# VentaConnected_ESP8266_V0_01_2018-09-03.net
KiCad netlist of a schematic drawn in EAGLE
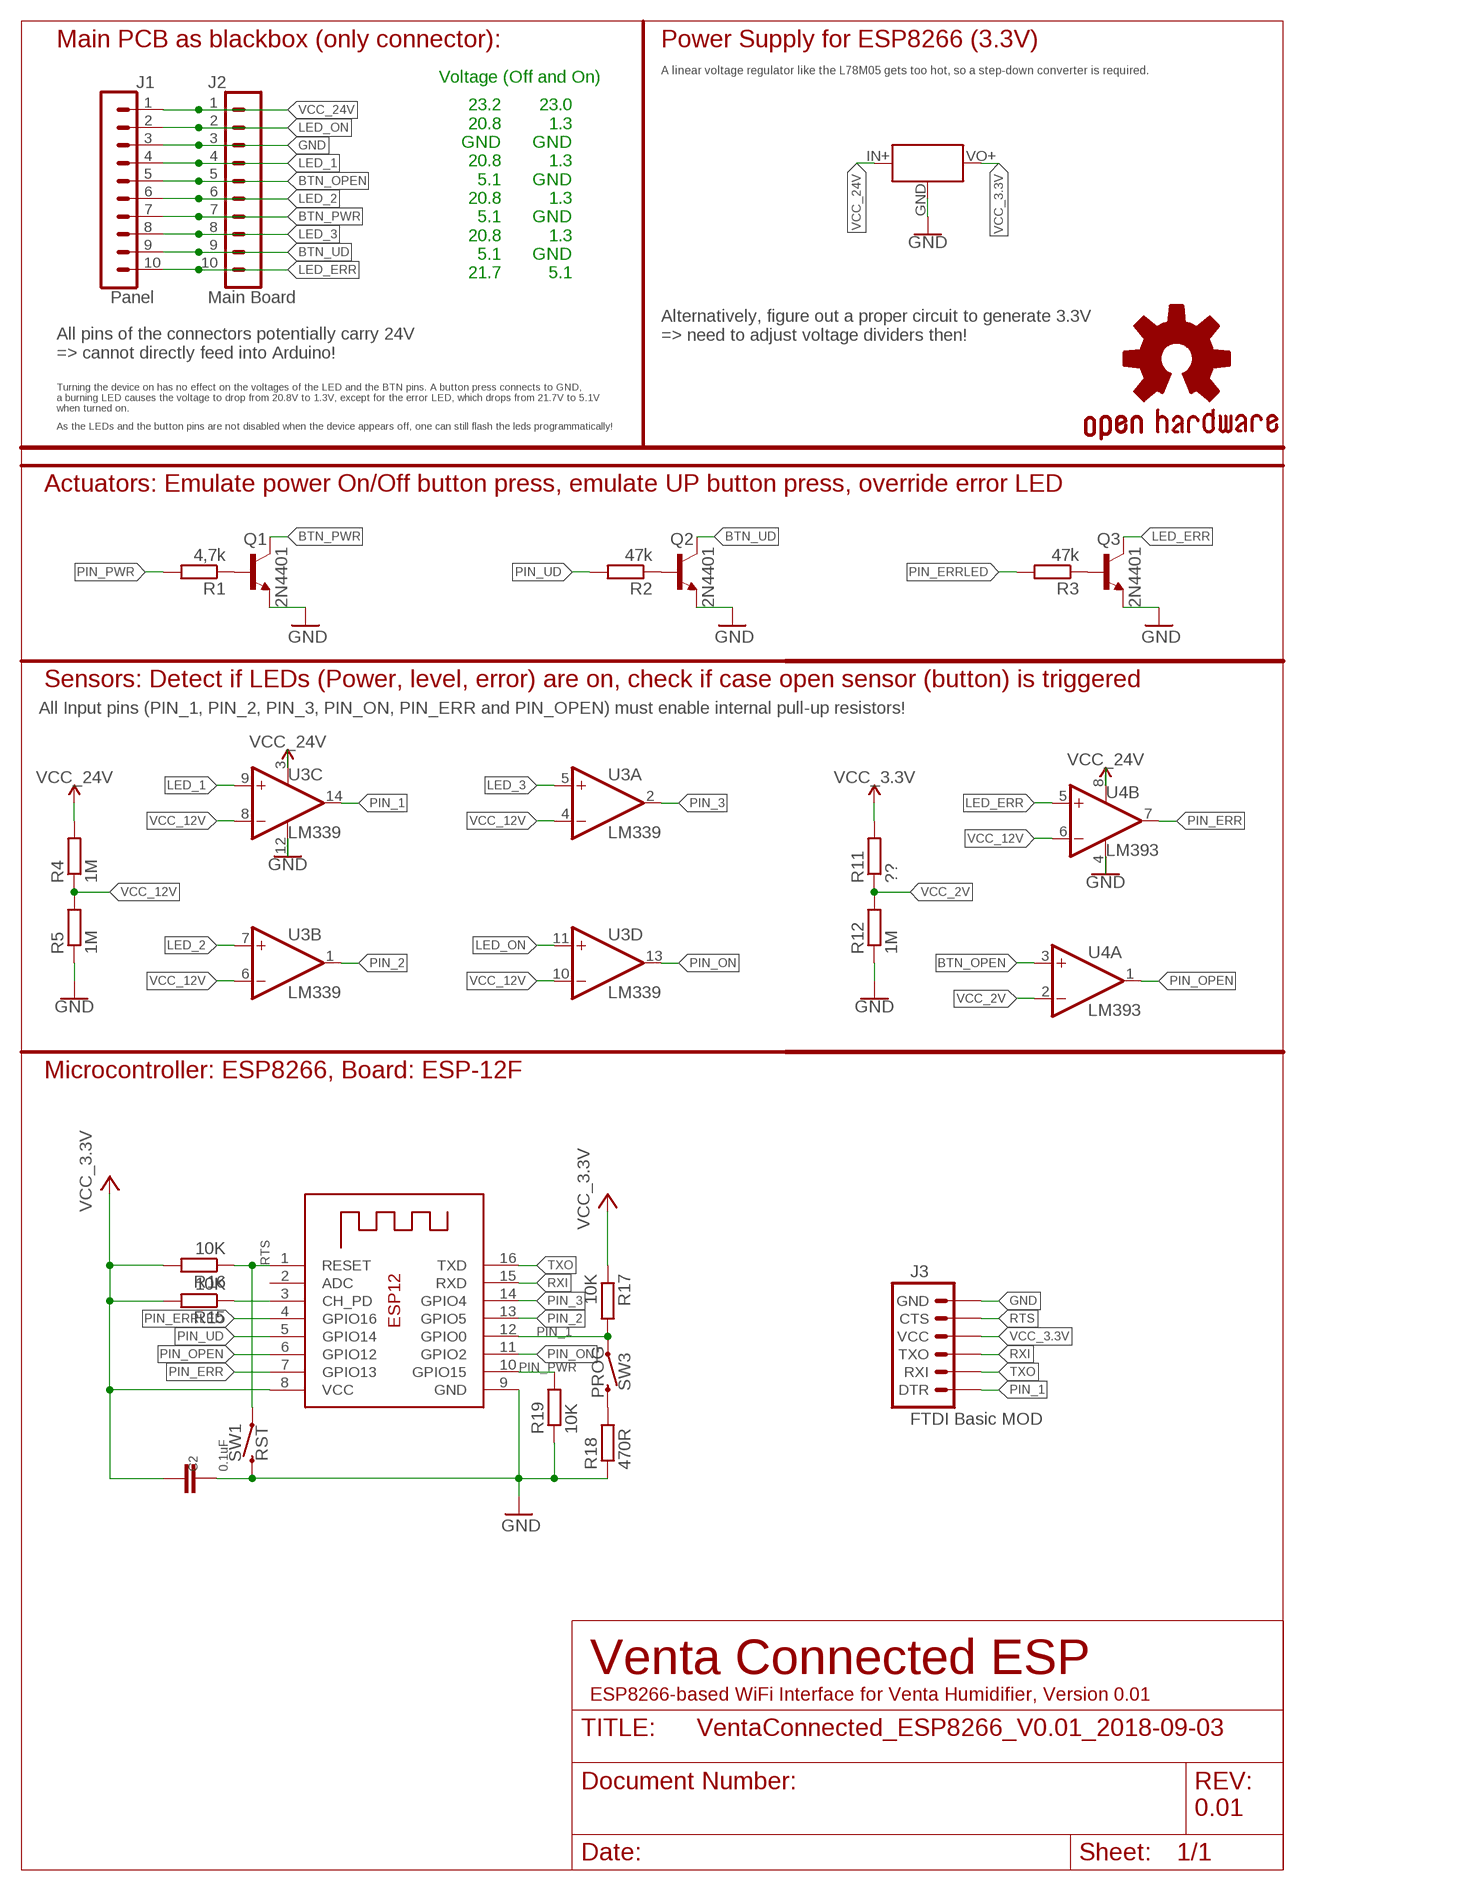
[diagram p0: schematic, sheet 1]

(export (version "E")
  (design (tool "Eeschema 10.0.6"))
  (components
    (comp (ref "C2")
      (value "0.1uF")
      (footprint "eagle-import:C0805")
      (libsource (lib "eagle-import") (part "C-EUC0805"))
    )
    (comp (ref "GOLD_ORB_SM1")
      (value "OSHWLOGO_GOLD_ORB_SM")
      (footprint "eagle-import:OSHW2")
      (libsource (lib "eagle-import") (part "OSHWLOGO_GOLD_ORB_SM"))
    )
    (comp (ref "J1")
      (value "Panel")
      (footprint "eagle-import:2X5-SHROUDED")
      (libsource (lib "eagle-import") (part "CONN_05X2SHD"))
    )
    (comp (ref "J2")
      (value "Main Board")
      (footprint "eagle-import:2X5")
      (libsource (lib "eagle-import") (part "CONN_05X2PTH"))
    )
    (comp (ref "J3")
      (value "FTDI Basic MOD")
      (footprint "eagle-import:1X06")
      (libsource (lib "eagle-import") (part "ARDUINO_SERIAL_PROGRAMPTH"))
    )
    (comp (ref "Q1")
      (value "2N4401")
      (footprint "eagle-import:SOT23-BEC")
      (libsource (lib "eagle-import") (part "-NPN-SOT23-BECMMBT4401LT1"))
    )
    (comp (ref "Q2")
      (value "2N4401")
      (footprint "eagle-import:SOT23-BEC")
      (libsource (lib "eagle-import") (part "-NPN-SOT23-BECMMBT4401LT1"))
    )
    (comp (ref "Q3")
      (value "2N4401")
      (footprint "eagle-import:SOT23-BEC")
      (libsource (lib "eagle-import") (part "-NPN-SOT23-BECMMBT4401LT1"))
    )
    (comp (ref "R1")
      (value "4,7k")
      (footprint "eagle-import:R0805")
      (libsource (lib "eagle-import") (part "resistor_348_R-EU_R0805"))
    )
    (comp (ref "R2")
      (value "47k")
      (footprint "eagle-import:R0805")
      (libsource (lib "eagle-import") (part "resistor_348_R-EU_R0805"))
    )
    (comp (ref "R3")
      (value "47k")
      (footprint "eagle-import:R0805")
      (libsource (lib "eagle-import") (part "resistor_348_R-EU_R0805"))
    )
    (comp (ref "R4")
      (value "1M")
      (footprint "eagle-import:R0805")
      (libsource (lib "eagle-import") (part "resistor_348_R-EU_R0805"))
    )
    (comp (ref "R5")
      (value "1M")
      (footprint "eagle-import:R0805")
      (libsource (lib "eagle-import") (part "resistor_348_R-EU_R0805"))
    )
    (comp (ref "R11")
      (value "??")
      (footprint "eagle-import:R0805")
      (libsource (lib "eagle-import") (part "resistor_348_R-EU_R0805"))
    )
    (comp (ref "R12")
      (value "1M")
      (footprint "eagle-import:R0805")
      (libsource (lib "eagle-import") (part "resistor_348_R-EU_R0805"))
    )
    (comp (ref "R15")
      (value "10K")
      (footprint "eagle-import:R0805")
      (libsource (lib "eagle-import") (part "R-EU_R0805"))
    )
    (comp (ref "R16")
      (value "10K")
      (footprint "eagle-import:R0805")
      (libsource (lib "eagle-import") (part "R-EU_R0805"))
    )
    (comp (ref "R17")
      (value "10K")
      (footprint "eagle-import:R0805")
      (libsource (lib "eagle-import") (part "R-EU_R0805"))
    )
    (comp (ref "R18")
      (value "470R")
      (footprint "eagle-import:R0805")
      (libsource (lib "eagle-import") (part "R-EU_R0805"))
    )
    (comp (ref "R19")
      (value "10K")
      (footprint "eagle-import:R0805")
      (libsource (lib "eagle-import") (part "R-EU_R0805"))
    )
    (comp (ref "SW1")
      (value "RST")
      (footprint "eagle-import:TACTILE_SWITCH_SMD_6.0X3.5MM")
      (libsource (lib "eagle-import") (part "MOMENTARY-SWITCH-SPST-SMD-6.0X3.5MM"))
    )
    (comp (ref "SW3")
      (value "PROG")
      (footprint "eagle-import:TACTILE_SWITCH_SMD_6.0X3.5MM")
      (libsource (lib "eagle-import") (part "MOMENTARY-SWITCH-SPST-SMD-6.0X3.5MM"))
    )
    (comp (ref "U2")
      (value "3.3V_BUCK_CONVERTER")
      (footprint "eagle-import:MINI_BUCK_CONVERTER_UPDOWN")
      (libsource (lib "eagle-import") (part "MINI_BUCK_CONVERTER_UPSIDEDOWN"))
    )
    (comp (ref "U3")
      (value "LM339")
      (footprint "eagle-import:SO14")
      (libsource (lib "eagle-import") (part "TLC339D"))
    )
    (comp (ref "U4")
      (value "LM393")
      (footprint "eagle-import:SO08")
      (libsource (lib "eagle-import") (part "LM393D"))
    )
    (comp (ref "X2")
      (value "ESP-12e")
      (footprint "eagle-import:ESP-12")
      (libsource (lib "eagle-import") (part "ESP-12"))
    )
  )
  (nets
    (net (code "1") (name "BTN_OPEN") (class "Default")
      (node (ref "J1") (pin "5") (pinfunction "5_5") (pintype "passive"))
      (node (ref "J2") (pin "5") (pinfunction "5_5") (pintype "passive"))
      (node (ref "U4") (pin "3") (pinfunction "+IN_3") (pintype "input"))
    )
    (net (code "2") (name "BTN_PWR") (class "Default")
      (node (ref "J1") (pin "7") (pinfunction "7_7") (pintype "passive"))
      (node (ref "J2") (pin "7") (pinfunction "7_7") (pintype "passive"))
      (node (ref "Q1") (pin "C") (pinfunction "C_C") (pintype "passive"))
    )
    (net (code "3") (name "BTN_UD") (class "Default")
      (node (ref "J1") (pin "9") (pinfunction "9_9") (pintype "passive"))
      (node (ref "J2") (pin "9") (pinfunction "9_9") (pintype "passive"))
      (node (ref "Q2") (pin "C") (pinfunction "C_C") (pintype "passive"))
    )
    (net (code "4") (name "GND") (class "Default")
      (node (ref "C2") (pin "1") (pinfunction "1_1") (pintype "passive"))
      (node (ref "J1") (pin "3") (pinfunction "3_3") (pintype "passive"))
      (node (ref "J2") (pin "3") (pinfunction "3_3") (pintype "passive"))
      (node (ref "J3") (pin "6") (pinfunction "GND_6") (pintype "passive"))
      (node (ref "Q1") (pin "E") (pinfunction "E_E") (pintype "passive"))
      (node (ref "Q2") (pin "E") (pinfunction "E_E") (pintype "passive"))
      (node (ref "Q3") (pin "E") (pinfunction "E_E") (pintype "passive"))
      (node (ref "R12") (pin "1") (pinfunction "1_1") (pintype "passive"))
      (node (ref "R18") (pin "1") (pinfunction "1_1") (pintype "passive"))
      (node (ref "R19") (pin "1") (pinfunction "1_1") (pintype "passive"))
      (node (ref "R5") (pin "1") (pinfunction "1_1") (pintype "passive"))
      (node (ref "SW1") (pin "2") (pinfunction "2_2") (pintype "passive"))
      (node (ref "U2") (pin "GND") (pinfunction "GND_GND") (pintype "bidirectional"))
      (node (ref "U3") (pin "12") (pinfunction "V-_12") (pintype "power_in"))
      (node (ref "U4") (pin "4") (pinfunction "V-_4") (pintype "power_in"))
      (node (ref "X2") (pin "9") (pinfunction "GND_9") (pintype "power_in"))
    )
    (net (code "5") (name "LED_1") (class "Default")
      (node (ref "J1") (pin "4") (pinfunction "4_4") (pintype "passive"))
      (node (ref "J2") (pin "4") (pinfunction "4_4") (pintype "passive"))
      (node (ref "U3") (pin "9") (pinfunction "+IN_9") (pintype "input"))
    )
    (net (code "6") (name "LED_2") (class "Default")
      (node (ref "J1") (pin "6") (pinfunction "6_6") (pintype "passive"))
      (node (ref "J2") (pin "6") (pinfunction "6_6") (pintype "passive"))
      (node (ref "U3") (pin "7") (pinfunction "+IN_7") (pintype "input"))
    )
    (net (code "7") (name "LED_3") (class "Default")
      (node (ref "J1") (pin "8") (pinfunction "8_8") (pintype "passive"))
      (node (ref "J2") (pin "8") (pinfunction "8_8") (pintype "passive"))
      (node (ref "U3") (pin "5") (pinfunction "+IN_5") (pintype "input"))
    )
    (net (code "8") (name "LED_ERR") (class "Default")
      (node (ref "J1") (pin "10") (pinfunction "10_10") (pintype "passive"))
      (node (ref "J2") (pin "10") (pinfunction "10_10") (pintype "passive"))
      (node (ref "Q3") (pin "C") (pinfunction "C_C") (pintype "passive"))
      (node (ref "U4") (pin "5") (pinfunction "+IN_5") (pintype "input"))
    )
    (net (code "9") (name "LED_ON") (class "Default")
      (node (ref "J1") (pin "2") (pinfunction "2_2") (pintype "passive"))
      (node (ref "J2") (pin "2") (pinfunction "2_2") (pintype "passive"))
      (node (ref "U3") (pin "11") (pinfunction "+IN_11") (pintype "input"))
    )
    (net (code "10") (name "Net-(Q1-PadB)") (class "Default")
      (node (ref "Q1") (pin "B") (pinfunction "B_B") (pintype "passive"))
      (node (ref "R1") (pin "1") (pinfunction "1_1") (pintype "passive"))
    )
    (net (code "11") (name "Net-(Q2-PadB)") (class "Default")
      (node (ref "Q2") (pin "B") (pinfunction "B_B") (pintype "passive"))
      (node (ref "R2") (pin "1") (pinfunction "1_1") (pintype "passive"))
    )
    (net (code "12") (name "Net-(Q3-PadB)") (class "Default")
      (node (ref "Q3") (pin "B") (pinfunction "B_B") (pintype "passive"))
      (node (ref "R3") (pin "1") (pinfunction "1_1") (pintype "passive"))
    )
    (net (code "13") (name "Net-(R18-Pad2)") (class "Default")
      (node (ref "R18") (pin "2") (pinfunction "2_2") (pintype "passive"))
      (node (ref "SW3") (pin "2") (pinfunction "2_2") (pintype "passive"))
    )
    (net (code "14") (name "Net-(X2-CH_PD)") (class "Default")
      (node (ref "R15") (pin "1") (pinfunction "1_1") (pintype "passive"))
      (node (ref "X2") (pin "3") (pinfunction "CH_PD_3") (pintype "input"))
    )
    (net (code "15") (name "PIN_1") (class "Default")
      (node (ref "J3") (pin "1") (pinfunction "DTR_1") (pintype "passive"))
      (node (ref "R17") (pin "2") (pinfunction "2_2") (pintype "passive"))
      (node (ref "SW3") (pin "1") (pinfunction "1_1") (pintype "passive"))
      (node (ref "U3") (pin "14") (pinfunction "OUT_14") (pintype "output"))
      (node (ref "X2") (pin "12") (pinfunction "GPIO0_12") (pintype "bidirectional"))
    )
    (net (code "16") (name "PIN_2") (class "Default")
      (node (ref "U3") (pin "1") (pinfunction "OUT_1") (pintype "output"))
      (node (ref "X2") (pin "13") (pinfunction "GPIO5_13") (pintype "bidirectional"))
    )
    (net (code "17") (name "PIN_3") (class "Default")
      (node (ref "U3") (pin "2") (pinfunction "OUT_2") (pintype "output"))
      (node (ref "X2") (pin "14") (pinfunction "GPIO4_14") (pintype "bidirectional"))
    )
    (net (code "18") (name "PIN_ERR") (class "Default")
      (node (ref "U4") (pin "7") (pinfunction "OUT_7") (pintype "output"))
      (node (ref "X2") (pin "7") (pinfunction "GPIO13_7") (pintype "bidirectional"))
    )
    (net (code "19") (name "PIN_ERRLED") (class "Default")
      (node (ref "R3") (pin "2") (pinfunction "2_2") (pintype "passive"))
      (node (ref "X2") (pin "4") (pinfunction "GPIO16_4") (pintype "bidirectional"))
    )
    (net (code "20") (name "PIN_ON") (class "Default")
      (node (ref "U3") (pin "13") (pinfunction "OUT_13") (pintype "output"))
      (node (ref "X2") (pin "11") (pinfunction "GPIO2_11") (pintype "bidirectional"))
    )
    (net (code "21") (name "PIN_OPEN") (class "Default")
      (node (ref "U4") (pin "1") (pinfunction "OUT_1") (pintype "output"))
      (node (ref "X2") (pin "6") (pinfunction "GPIO12_6") (pintype "bidirectional"))
    )
    (net (code "22") (name "PIN_PWR") (class "Default")
      (node (ref "R1") (pin "2") (pinfunction "2_2") (pintype "passive"))
      (node (ref "R19") (pin "2") (pinfunction "2_2") (pintype "passive"))
      (node (ref "X2") (pin "10") (pinfunction "GPIO15_10") (pintype "bidirectional"))
    )
    (net (code "23") (name "PIN_UD") (class "Default")
      (node (ref "R2") (pin "2") (pinfunction "2_2") (pintype "passive"))
      (node (ref "X2") (pin "5") (pinfunction "GPIO14_5") (pintype "bidirectional"))
    )
    (net (code "24") (name "RTS") (class "Default")
      (node (ref "J3") (pin "5") (pinfunction "CTS_5") (pintype "passive"))
      (node (ref "R16") (pin "1") (pinfunction "1_1") (pintype "passive"))
      (node (ref "SW1") (pin "1") (pinfunction "1_1") (pintype "passive"))
      (node (ref "X2") (pin "1") (pinfunction "RESET_1") (pintype "input"))
    )
    (net (code "25") (name "RXI") (class "Default")
      (node (ref "J3") (pin "3") (pinfunction "TXO_3") (pintype "passive"))
      (node (ref "X2") (pin "15") (pinfunction "RXD_15") (pintype "input"))
    )
    (net (code "26") (name "TXO") (class "Default")
      (node (ref "J3") (pin "2") (pinfunction "RXI_2") (pintype "passive"))
      (node (ref "X2") (pin "16") (pinfunction "TXD_16") (pintype "output"))
    )
    (net (code "27") (name "VCC_2V") (class "Default")
      (node (ref "R11") (pin "1") (pinfunction "1_1") (pintype "passive"))
      (node (ref "R12") (pin "2") (pinfunction "2_2") (pintype "passive"))
      (node (ref "U4") (pin "2") (pinfunction "-IN_2") (pintype "input"))
    )
    (net (code "28") (name "VCC_3.3V") (class "Default")
      (node (ref "C2") (pin "2") (pinfunction "2_2") (pintype "passive"))
      (node (ref "J3") (pin "4") (pinfunction "VCC_4") (pintype "passive"))
      (node (ref "R11") (pin "2") (pinfunction "2_2") (pintype "passive"))
      (node (ref "R15") (pin "2") (pinfunction "2_2") (pintype "passive"))
      (node (ref "R16") (pin "2") (pinfunction "2_2") (pintype "passive"))
      (node (ref "R17") (pin "1") (pinfunction "1_1") (pintype "passive"))
      (node (ref "U2") (pin "VO+") (pinfunction "VOUT_VO+") (pintype "power_in"))
      (node (ref "X2") (pin "8") (pinfunction "VCC_8") (pintype "power_in"))
    )
    (net (code "29") (name "VCC_12V") (class "Default")
      (node (ref "R4") (pin "1") (pinfunction "1_1") (pintype "passive"))
      (node (ref "R5") (pin "2") (pinfunction "2_2") (pintype "passive"))
      (node (ref "U3") (pin "10") (pinfunction "-IN_10") (pintype "input"))
      (node (ref "U3") (pin "4") (pinfunction "-IN_4") (pintype "input"))
      (node (ref "U3") (pin "6") (pinfunction "-IN_6") (pintype "input"))
      (node (ref "U3") (pin "8") (pinfunction "-IN_8") (pintype "input"))
      (node (ref "U4") (pin "6") (pinfunction "-IN_6") (pintype "input"))
    )
    (net (code "30") (name "VCC_24V") (class "Default")
      (node (ref "J1") (pin "1") (pinfunction "1_1") (pintype "passive"))
      (node (ref "J2") (pin "1") (pinfunction "1_1") (pintype "passive"))
      (node (ref "R4") (pin "2") (pinfunction "2_2") (pintype "passive"))
      (node (ref "U2") (pin "IN+") (pinfunction "VIN_IN+") (pintype "input"))
      (node (ref "U3") (pin "3") (pinfunction "V+_3") (pintype "power_in"))
      (node (ref "U4") (pin "8") (pinfunction "V+_8") (pintype "power_in"))
    )
    (net (code "31") (name "unconnected-(X2-ADC-Pad2)") (class "Default")
      (node (ref "X2") (pin "2") (pinfunction "ADC_2") (pintype "passive"))
    )
  )
)
